# mpustm.net
KiCad netlist of a schematic drawn in Altium Designer
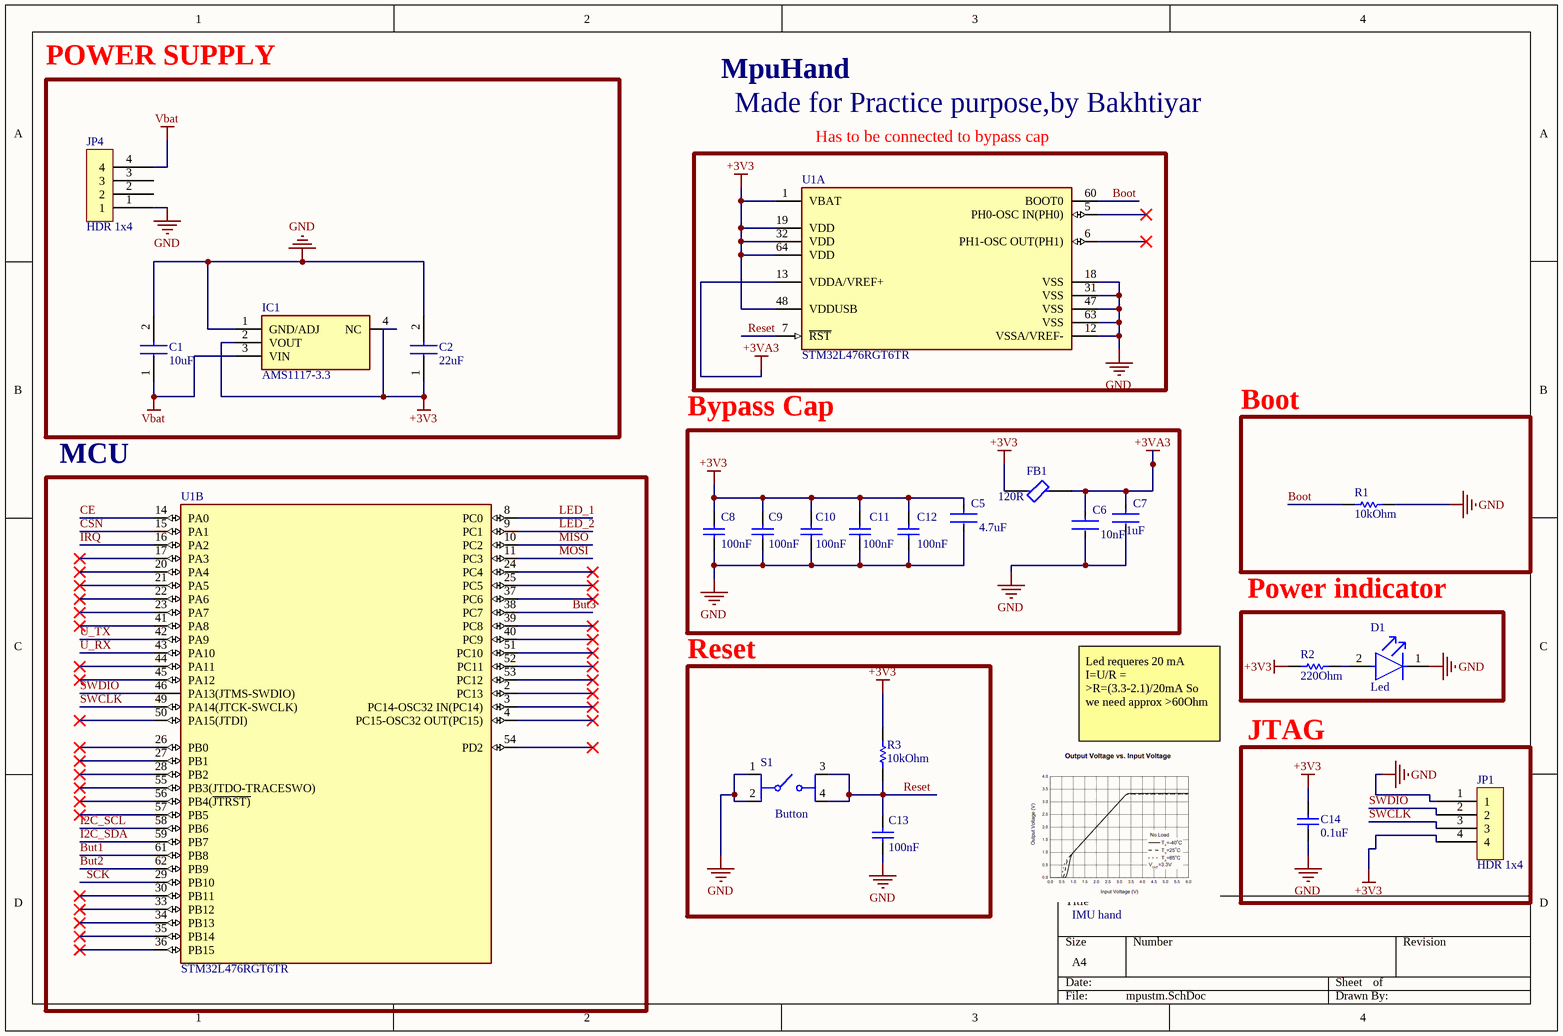
[diagram p0: mpustm.SchDoc]

(export (version "E")
  (design (tool "Eeschema 10.0.6"))
  (components
    (comp (ref "C1")
      (value "10uF")
      (footprint "SamacSys:CAPC2012X140N")
      (description "Capacitor")
      (fields
        (field (name "MANUFACTURER_PART_NUMBER") "CL21A106KOQNNNE")
        (field (name "MOUSER PART NUMBER") "187-CL21A106KOQNNNE")
      )
      (libsource (lib "*") (part "CL21A106KOQNNNE"))
    )
    (comp (ref "C2")
      (value "22uF")
      (footprint "SamacSys:CAPC2012X140N")
      (description "Capacitor")
      (fields
        (field (name "MANUFACTURER_PART_NUMBER") "CL21A226MQQNNNE")
        (field (name "MOUSER PART NUMBER") "187-CL21A226MQQNNNE")
      )
      (libsource (lib "*") (part "CL21A226MQQNNNE"))
    )
    (comp (ref "C5")
      (value "4.7uF")
      (footprint "FP-CL282-IPC_C")
      (description "Cap Ceramic 4.7uF 10V X5R ±20% SMD 0402 +85°C Paper T/R")
      (fields (field (name "TOLERANCE") "20%"))
      (libsource (lib "Altium Content Vault") (part "b4654b650e69147ec39a6b967a45e02"))
    )
    (comp (ref "C6")
      (value "10nF")
      (footprint "FP-CL165-IPC_C")
      (description "Cap Ceramic 10nF 50V X7R ±10% SMD 0402 +125°C Paper T/R")
      (fields (field (name "VOLTAGE") "50V") (field (name "TOLERANCE") "10%"))
      (libsource (lib "Altium Content Vault") (part "b4654b650e69147ec39a6b967a45e02"))
    )
    (comp (ref "C7")
      (value "1uF")
      (footprint "FP-CL511-IPC_C")
      (description "Cap Ceramic 1uF 10V X5R ±10% SMD 0402 +85°C Paper T/R")
      (fields (field (name "TOLERANCE") "10%"))
      (libsource (lib "Altium Content Vault") (part "b4654b650e69147ec39a6b967a45e02"))
    )
    (comp (ref "C8")
      (value "100nF")
      (footprint "CAPC1050X55X23ML05T13")
      (description "Chip Capacitor, 100 nF, +/- 10%, 16 V, -55 to 125 degC, 0402 (1005 Metric), RoHS, Tape and Reel")
      (fields (field (name "MANUFACTURER") "Samsung Electro-Mechanics"))
      (libsource (lib "Altium Content Vault") (part "CAP-NP-2"))
    )
    (comp (ref "C9")
      (value "100nF")
      (footprint "CAPC1050X55X23ML05T13")
      (description "Chip Capacitor, 100 nF, +/- 10%, 16 V, -55 to 125 degC, 0402 (1005 Metric), RoHS, Tape and Reel")
      (fields (field (name "MANUFACTURER") "Samsung Electro-Mechanics"))
      (libsource (lib "Altium Content Vault") (part "CAP-NP-2"))
    )
    (comp (ref "C10")
      (value "100nF")
      (footprint "CAPC1050X55X23ML05T13")
      (description "Chip Capacitor, 100 nF, +/- 10%, 16 V, -55 to 125 degC, 0402 (1005 Metric), RoHS, Tape and Reel")
      (fields (field (name "MANUFACTURER") "Samsung Electro-Mechanics"))
      (libsource (lib "Altium Content Vault") (part "CAP-NP-2"))
    )
    (comp (ref "C11")
      (value "100nF")
      (footprint "CAPC1050X55X23ML05T13")
      (description "Chip Capacitor, 100 nF, +/- 10%, 16 V, -55 to 125 degC, 0402 (1005 Metric), RoHS, Tape and Reel")
      (fields (field (name "MANUFACTURER") "Samsung Electro-Mechanics"))
      (libsource (lib "Altium Content Vault") (part "CAP-NP-2"))
    )
    (comp (ref "C12")
      (value "100nF")
      (footprint "CAPC1050X55X23ML05T13")
      (description "Chip Capacitor, 100 nF, +/- 10%, 16 V, -55 to 125 degC, 0402 (1005 Metric), RoHS, Tape and Reel")
      (fields (field (name "MANUFACTURER") "Samsung Electro-Mechanics"))
      (libsource (lib "Altium Content Vault") (part "CAP-NP-2"))
    )
    (comp (ref "C13")
      (value "100nF")
      (footprint "CAPC1050X55X23ML05T13")
      (description "Chip Capacitor, 100 nF, +/- 10%, 16 V, -55 to 125 degC, 0402 (1005 Metric), RoHS, Tape and Reel")
      (fields (field (name "MANUFACTURER") "Samsung Electro-Mechanics"))
      (libsource (lib "Altium Content Vault") (part "CAP-NP-2"))
    )
    (comp (ref "C14")
      (value "0.1uF")
      (footprint "CAPC1050X55X23ML05T13")
      (description "Chip Capacitor, 100 nF, +/- 10%, 16 V, -55 to 125 degC, 0402 (1005 Metric), RoHS, Tape and Reel")
      (fields (field (name "MANUFACTURER") "Samsung Electro-Mechanics"))
      (libsource (lib "Altium Content Vault") (part "CAP-NP-2"))
    )
    (comp (ref "D1")
      (value "Led")
      (footprint "FP-LTST-C191GKT-MFG")
      (description "LED GREEN CLEAR CHIP SMD")
      (libsource (lib "Altium Content Vault") (part "8706943c75ba83719d021d2fdc84c58"))
    )
    (comp (ref "FB1")
      (value "120R")
      (footprint "FP-BLM18-0_15-t0_8-IPC_C")
      (description "Chip Ferrite Bead, 0603, 5Ω @ 100MHz, 0.05Ω, 25%, 800mA")
      (fields (field (name "TOLERANCE") "25%"))
      (libsource (lib "Altium Content Vault") (part "5f30dd21d616792df468990f7003faa"))
    )
    (comp (ref "IC1")
      (value "AMS1117-3.3")
      (footprint "SamacSys:SOT229P700X180-4N")
      (description "Integrated Circuit")
      (libsource (lib "*") (part "AMS1117-3.3"))
    )
    (comp (ref "JP1")
      (value "HDR 1x4")
      (footprint "HDR Male1_4 2.54mm")
      (description "CONN HEADER VERT 4POS 2.54MM")
      (fields
        (field (name "MANUFACTURER") "Amphenol FCI")
        (field (name "MANUFACTURER PART NUMBER") "68001-204HLF")
      )
      (libsource (lib "Male_Header_1_4 2.54mm") (part "68001-204HLF"))
    )
    (comp (ref "JP4")
      (value "HDR 1x4")
      (footprint "HDR Male1_4 2.54mm")
      (description "CONN HEADER VERT 4POS 2.54MM")
      (fields
        (field (name "MANUFACTURER") "Amphenol FCI")
        (field (name "MANUFACTURER PART NUMBER") "68001-204HLF")
      )
      (libsource (lib "") (part "68001-204HLF_1"))
    )
    (comp (ref "R1")
      (value "10kOhm")
      (footprint "RESC2013X60X35ML10T20")
      (description "Chip Resistor, 10 KOhm, +/- 5%, 0.125 W, -55 to 155 degC, 0805 (2012 Metric), RoHS, Tape and Reel")
      (fields (field (name "MANUFACTURER") "Yageo"))
      (libsource (lib "Altium Content Vault") (part "RES-2"))
    )
    (comp (ref "R2")
      (value "220Ohm")
      (footprint "RESC1608X55X25ML10T15")
      (libsource (lib "Altium Content Vault") (part "RES-2"))
    )
    (comp (ref "R3")
      (value "10kOhm")
      (footprint "RESC2013X60X35ML10T20")
      (description "Chip Resistor, 10 KOhm, +/- 5%, 0.125 W, -55 to 155 degC, 0805 (2012 Metric), RoHS, Tape and Reel")
      (fields (field (name "MANUFACTURER") "Yageo"))
      (libsource (lib "Altium Content Vault") (part "RES-2"))
    )
    (comp (ref "S1")
      (value "Button")
      (footprint "SamacSys:GSPTS004901")
      (description "Switch (4-Pin Push)")
      (fields (field (name "MANUFACTURER_PART_NUMBER") "GSPTS004901"))
      (libsource (lib "SamacSys") (part "GSPTS004901"))
    )
    (comp (ref "U1")
      (value "STM32L476RGT6TR")
      (footprint "FP-LQFP64-5W-MFG")
      (description "IC MCU 32BIT 1MB FLASH 64LQFP")
      (fields
        (field (name "OCTOPART") "https://octopart.com/stm32l476rgt6tr-stmicroelectronics-74146120")
        (field (name "MANUFACTURER") "STMicroelectronics")
      )
      (libsource (lib "Altium Content Vault") (part "87b63bd17e71f2d821570a63d08c5bc"))
    )
  )
  (nets
    (net (code "1") (name "+3V3") (class "Default")
      (node (ref "C10") (pin "2") (pinfunction "2_2") (pintype "passive"))
      (node (ref "C11") (pin "2") (pinfunction "2_2") (pintype "passive"))
      (node (ref "C12") (pin "2") (pinfunction "2_2") (pintype "passive"))
      (node (ref "C14") (pin "2") (pinfunction "2_2") (pintype "passive"))
      (node (ref "C2") (pin "1") (pinfunction "1_1") (pintype "passive"))
      (node (ref "C5") (pin "1") (pinfunction "1_1") (pintype "passive"))
      (node (ref "C8") (pin "2") (pinfunction "2_2") (pintype "passive"))
      (node (ref "C9") (pin "2") (pinfunction "2_2") (pintype "passive"))
      (node (ref "FB1") (pin "1") (pinfunction "1_1") (pintype "passive"))
      (node (ref "IC1") (pin "2") (pinfunction "VOUT_2") (pintype "passive"))
      (node (ref "IC1") (pin "4") (pinfunction "NC_4") (pintype "passive"))
      (node (ref "JP1") (pin "4") (pinfunction "4_4") (pintype "passive"))
      (node (ref "R2") (pin "2") (pinfunction "2_2") (pintype "passive"))
      (node (ref "R3") (pin "2") (pinfunction "2_2") (pintype "passive"))
      (node (ref "U1") (pin "1") (pinfunction "VBAT_1") (pintype "power_in"))
      (node (ref "U1") (pin "19") (pinfunction "VDD_19") (pintype "power_in"))
      (node (ref "U1") (pin "32") (pinfunction "VDD_32") (pintype "power_in"))
      (node (ref "U1") (pin "48") (pinfunction "VDDUSB_48") (pintype "power_in"))
      (node (ref "U1") (pin "64") (pinfunction "VDD_64") (pintype "power_in"))
    )
    (net (code "2") (name "+3VA3") (class "Default")
      (node (ref "C6") (pin "1") (pinfunction "1_1") (pintype "passive"))
      (node (ref "C7") (pin "1") (pinfunction "1_1") (pintype "passive"))
      (node (ref "FB1") (pin "2") (pinfunction "2_2") (pintype "passive"))
      (node (ref "U1") (pin "13") (pinfunction "VDDA/VREF+_13") (pintype "power_in"))
    )
    (net (code "3") (name "/Boot") (class "Default")
      (node (ref "R1") (pin "2") (pinfunction "2_2") (pintype "passive"))
      (node (ref "U1") (pin "60") (pinfunction "BOOT0_60") (pintype "passive"))
    )
    (net (code "4") (name "/But1") (class "Default")
      (node (ref "U1") (pin "61") (pinfunction "PB8_61") (pintype "bidirectional"))
    )
    (net (code "5") (name "/But2") (class "Default")
      (node (ref "U1") (pin "62") (pinfunction "PB9_62") (pintype "bidirectional"))
    )
    (net (code "6") (name "/But3") (class "Default")
      (node (ref "U1") (pin "38") (pinfunction "PC7_38") (pintype "bidirectional"))
    )
    (net (code "7") (name "/CE") (class "Default")
      (node (ref "U1") (pin "14") (pinfunction "PA0_14") (pintype "bidirectional"))
    )
    (net (code "8") (name "/CSN") (class "Default")
      (node (ref "U1") (pin "15") (pinfunction "PA1_15") (pintype "bidirectional"))
    )
    (net (code "9") (name "/I2C_SCL") (class "Default")
      (node (ref "U1") (pin "58") (pinfunction "PB6_58") (pintype "bidirectional"))
    )
    (net (code "10") (name "/I2C_SDA") (class "Default")
      (node (ref "U1") (pin "59") (pinfunction "PB7_59") (pintype "bidirectional"))
    )
    (net (code "11") (name "/IRQ") (class "Default")
      (node (ref "U1") (pin "16") (pinfunction "PA2_16") (pintype "bidirectional"))
    )
    (net (code "12") (name "/LED_1") (class "Default")
      (node (ref "U1") (pin "8") (pinfunction "PC0_8") (pintype "bidirectional"))
    )
    (net (code "13") (name "/LED_2") (class "Default")
      (node (ref "U1") (pin "9") (pinfunction "PC1_9") (pintype "bidirectional"))
    )
    (net (code "14") (name "/MISO") (class "Default")
      (node (ref "U1") (pin "10") (pinfunction "PC2_10") (pintype "bidirectional"))
    )
    (net (code "15") (name "/MOSI") (class "Default")
      (node (ref "U1") (pin "11") (pinfunction "PC3_11") (pintype "bidirectional"))
    )
    (net (code "16") (name "/Reset") (class "Default")
      (node (ref "C13") (pin "2") (pinfunction "2_2") (pintype "passive"))
      (node (ref "R3") (pin "1") (pinfunction "1_1") (pintype "passive"))
      (node (ref "S1") (pin "3") (pinfunction "NO_1_3") (pintype "passive"))
      (node (ref "S1") (pin "4") (pinfunction "NO_2_4") (pintype "passive"))
      (node (ref "U1") (pin "7") (pinfunction "~{RST}_7") (pintype "input"))
    )
    (net (code "17") (name "/SCK") (class "Default")
      (node (ref "U1") (pin "29") (pinfunction "PB10_29") (pintype "bidirectional"))
    )
    (net (code "18") (name "/SWCLK") (class "Default")
      (node (ref "JP1") (pin "3") (pinfunction "3_3") (pintype "passive"))
      (node (ref "U1") (pin "49") (pinfunction "PA14(JTCK-SWCLK)_49") (pintype "bidirectional"))
    )
    (net (code "19") (name "/SWDIO") (class "Default")
      (node (ref "JP1") (pin "2") (pinfunction "2_2") (pintype "passive"))
      (node (ref "U1") (pin "46") (pinfunction "PA13(JTMS-SWDIO)_46") (pintype "power_in"))
    )
    (net (code "20") (name "/U_RX") (class "Default")
      (node (ref "U1") (pin "43") (pinfunction "PA10_43") (pintype "bidirectional"))
    )
    (net (code "21") (name "/U_TX") (class "Default")
      (node (ref "U1") (pin "42") (pinfunction "PA9_42") (pintype "bidirectional"))
    )
    (net (code "22") (name "GND") (class "Default")
      (node (ref "C1") (pin "2") (pinfunction "2_2") (pintype "passive"))
      (node (ref "C10") (pin "1") (pinfunction "1_1") (pintype "passive"))
      (node (ref "C11") (pin "1") (pinfunction "1_1") (pintype "passive"))
      (node (ref "C12") (pin "1") (pinfunction "1_1") (pintype "passive"))
      (node (ref "C13") (pin "1") (pinfunction "1_1") (pintype "passive"))
      (node (ref "C14") (pin "1") (pinfunction "1_1") (pintype "passive"))
      (node (ref "C2") (pin "2") (pinfunction "2_2") (pintype "passive"))
      (node (ref "C5") (pin "2") (pinfunction "2_2") (pintype "passive"))
      (node (ref "C6") (pin "2") (pinfunction "2_2") (pintype "passive"))
      (node (ref "C7") (pin "2") (pinfunction "2_2") (pintype "passive"))
      (node (ref "C8") (pin "1") (pinfunction "1_1") (pintype "passive"))
      (node (ref "C9") (pin "1") (pinfunction "1_1") (pintype "passive"))
      (node (ref "D1") (pin "1") (pinfunction "C_1") (pintype "passive"))
      (node (ref "IC1") (pin "1") (pinfunction "GND/ADJ_1") (pintype "passive"))
      (node (ref "JP1") (pin "1") (pinfunction "1_1") (pintype "passive"))
      (node (ref "JP4") (pin "1") (pinfunction "1_1") (pintype "passive"))
      (node (ref "R1") (pin "1") (pinfunction "1_1") (pintype "passive"))
      (node (ref "S1") (pin "1") (pinfunction "COM_1_1") (pintype "passive"))
      (node (ref "S1") (pin "2") (pinfunction "COM_2_2") (pintype "passive"))
      (node (ref "U1") (pin "12") (pinfunction "VSSA/VREF-_12") (pintype "power_in"))
      (node (ref "U1") (pin "18") (pinfunction "VSS_18") (pintype "power_in"))
      (node (ref "U1") (pin "31") (pinfunction "VSS_31") (pintype "power_in"))
      (node (ref "U1") (pin "47") (pinfunction "VSS_47") (pintype "power_in"))
      (node (ref "U1") (pin "63") (pinfunction "VSS_63") (pintype "power_in"))
    )
    (net (code "23") (name "Net-(D1-A)") (class "Default")
      (node (ref "D1") (pin "2") (pinfunction "A_2") (pintype "passive"))
      (node (ref "R2") (pin "1") (pinfunction "1_1") (pintype "passive"))
    )
    (net (code "24") (name "Vbat") (class "Default")
      (node (ref "C1") (pin "1") (pinfunction "1_1") (pintype "passive"))
      (node (ref "IC1") (pin "3") (pinfunction "VIN_3") (pintype "passive"))
      (node (ref "JP4") (pin "4") (pinfunction "4_4") (pintype "passive"))
    )
    (net (code "25") (name "unconnected-(JP4-Pad2)") (class "Default")
      (node (ref "JP4") (pin "2") (pinfunction "2_2") (pintype "passive"))
    )
    (net (code "26") (name "unconnected-(JP4-Pad3)") (class "Default")
      (node (ref "JP4") (pin "3") (pinfunction "3_3") (pintype "passive"))
    )
    (net (code "27") (name "unconnected-(U1A-PH0-OSC_IN(PH0)-Pad5)") (class "Default")
      (node (ref "U1") (pin "5") (pinfunction "PH0-OSC_IN(PH0)_5") (pintype "bidirectional+no_connect"))
    )
    (net (code "28") (name "unconnected-(U1A-PH1-OSC_OUT(PH1)-Pad6)") (class "Default")
      (node (ref "U1") (pin "6") (pinfunction "PH1-OSC_OUT(PH1)_6") (pintype "bidirectional+no_connect"))
    )
    (net (code "29") (name "unconnected-(U1B-PA3-Pad17)") (class "Default")
      (node (ref "U1") (pin "17") (pinfunction "PA3_17") (pintype "bidirectional+no_connect"))
    )
    (net (code "30") (name "unconnected-(U1B-PA4-Pad20)") (class "Default")
      (node (ref "U1") (pin "20") (pinfunction "PA4_20") (pintype "bidirectional+no_connect"))
    )
    (net (code "31") (name "unconnected-(U1B-PA5-Pad21)") (class "Default")
      (node (ref "U1") (pin "21") (pinfunction "PA5_21") (pintype "bidirectional+no_connect"))
    )
    (net (code "32") (name "unconnected-(U1B-PA6-Pad22)") (class "Default")
      (node (ref "U1") (pin "22") (pinfunction "PA6_22") (pintype "bidirectional+no_connect"))
    )
    (net (code "33") (name "unconnected-(U1B-PA7-Pad23)") (class "Default")
      (node (ref "U1") (pin "23") (pinfunction "PA7_23") (pintype "bidirectional+no_connect"))
    )
    (net (code "34") (name "unconnected-(U1B-PA8-Pad41)") (class "Default")
      (node (ref "U1") (pin "41") (pinfunction "PA8_41") (pintype "bidirectional+no_connect"))
    )
    (net (code "35") (name "unconnected-(U1B-PA11-Pad44)") (class "Default")
      (node (ref "U1") (pin "44") (pinfunction "PA11_44") (pintype "bidirectional+no_connect"))
    )
    (net (code "36") (name "unconnected-(U1B-PA12-Pad45)") (class "Default")
      (node (ref "U1") (pin "45") (pinfunction "PA12_45") (pintype "bidirectional+no_connect"))
    )
    (net (code "37") (name "unconnected-(U1B-PA15(JTDI)-Pad50)") (class "Default")
      (node (ref "U1") (pin "50") (pinfunction "PA15(JTDI)_50") (pintype "bidirectional+no_connect"))
    )
    (net (code "38") (name "unconnected-(U1B-PB0-Pad26)") (class "Default")
      (node (ref "U1") (pin "26") (pinfunction "PB0_26") (pintype "bidirectional+no_connect"))
    )
    (net (code "39") (name "unconnected-(U1B-PB1-Pad27)") (class "Default")
      (node (ref "U1") (pin "27") (pinfunction "PB1_27") (pintype "bidirectional+no_connect"))
    )
    (net (code "40") (name "unconnected-(U1B-PB2-Pad28)") (class "Default")
      (node (ref "U1") (pin "28") (pinfunction "PB2_28") (pintype "bidirectional+no_connect"))
    )
    (net (code "41") (name "unconnected-(U1B-PB3(JTDO-TRACESWO)-Pad55)") (class "Default")
      (node (ref "U1") (pin "55") (pinfunction "PB3(JTDO-TRACESWO)_55") (pintype "bidirectional+no_connect"))
    )
    (net (code "42") (name "unconnected-(U1B-PB4(~{JTRST)}-Pad56)") (class "Default")
      (node (ref "U1") (pin "56") (pinfunction "PB4(~{JTRST)}_56") (pintype "bidirectional+no_connect"))
    )
    (net (code "43") (name "unconnected-(U1B-PB5-Pad57)") (class "Default")
      (node (ref "U1") (pin "57") (pinfunction "PB5_57") (pintype "bidirectional+no_connect"))
    )
    (net (code "44") (name "unconnected-(U1B-PB11-Pad30)") (class "Default")
      (node (ref "U1") (pin "30") (pinfunction "PB11_30") (pintype "bidirectional+no_connect"))
    )
    (net (code "45") (name "unconnected-(U1B-PB12-Pad33)") (class "Default")
      (node (ref "U1") (pin "33") (pinfunction "PB12_33") (pintype "bidirectional+no_connect"))
    )
    (net (code "46") (name "unconnected-(U1B-PB13-Pad34)") (class "Default")
      (node (ref "U1") (pin "34") (pinfunction "PB13_34") (pintype "bidirectional+no_connect"))
    )
    (net (code "47") (name "unconnected-(U1B-PB14-Pad35)") (class "Default")
      (node (ref "U1") (pin "35") (pinfunction "PB14_35") (pintype "bidirectional+no_connect"))
    )
    (net (code "48") (name "unconnected-(U1B-PB15-Pad36)") (class "Default")
      (node (ref "U1") (pin "36") (pinfunction "PB15_36") (pintype "bidirectional+no_connect"))
    )
    (net (code "49") (name "unconnected-(U1B-PC4-Pad24)") (class "Default")
      (node (ref "U1") (pin "24") (pinfunction "PC4_24") (pintype "bidirectional+no_connect"))
    )
    (net (code "50") (name "unconnected-(U1B-PC5-Pad25)") (class "Default")
      (node (ref "U1") (pin "25") (pinfunction "PC5_25") (pintype "bidirectional+no_connect"))
    )
    (net (code "51") (name "unconnected-(U1B-PC6-Pad37)") (class "Default")
      (node (ref "U1") (pin "37") (pinfunction "PC6_37") (pintype "bidirectional+no_connect"))
    )
    (net (code "52") (name "unconnected-(U1B-PC8-Pad39)") (class "Default")
      (node (ref "U1") (pin "39") (pinfunction "PC8_39") (pintype "bidirectional+no_connect"))
    )
    (net (code "53") (name "unconnected-(U1B-PC9-Pad40)") (class "Default")
      (node (ref "U1") (pin "40") (pinfunction "PC9_40") (pintype "bidirectional+no_connect"))
    )
    (net (code "54") (name "unconnected-(U1B-PC10-Pad51)") (class "Default")
      (node (ref "U1") (pin "51") (pinfunction "PC10_51") (pintype "bidirectional+no_connect"))
    )
    (net (code "55") (name "unconnected-(U1B-PC11-Pad52)") (class "Default")
      (node (ref "U1") (pin "52") (pinfunction "PC11_52") (pintype "bidirectional+no_connect"))
    )
    (net (code "56") (name "unconnected-(U1B-PC12-Pad53)") (class "Default")
      (node (ref "U1") (pin "53") (pinfunction "PC12_53") (pintype "bidirectional+no_connect"))
    )
    (net (code "57") (name "unconnected-(U1B-PC13-Pad2)") (class "Default")
      (node (ref "U1") (pin "2") (pinfunction "PC13_2") (pintype "bidirectional+no_connect"))
    )
    (net (code "58") (name "unconnected-(U1B-PC14-OSC32_IN(PC14)-Pad3)") (class "Default")
      (node (ref "U1") (pin "3") (pinfunction "PC14-OSC32_IN(PC14)_3") (pintype "bidirectional+no_connect"))
    )
    (net (code "59") (name "unconnected-(U1B-PC15-OSC32_OUT(PC15)-Pad4)") (class "Default")
      (node (ref "U1") (pin "4") (pinfunction "PC15-OSC32_OUT(PC15)_4") (pintype "bidirectional+no_connect"))
    )
    (net (code "60") (name "unconnected-(U1B-PD2-Pad54)") (class "Default")
      (node (ref "U1") (pin "54") (pinfunction "PD2_54") (pintype "bidirectional+no_connect"))
    )
  )
)
